# Interface.net
KiCad netlist of a schematic drawn in Altium Designer
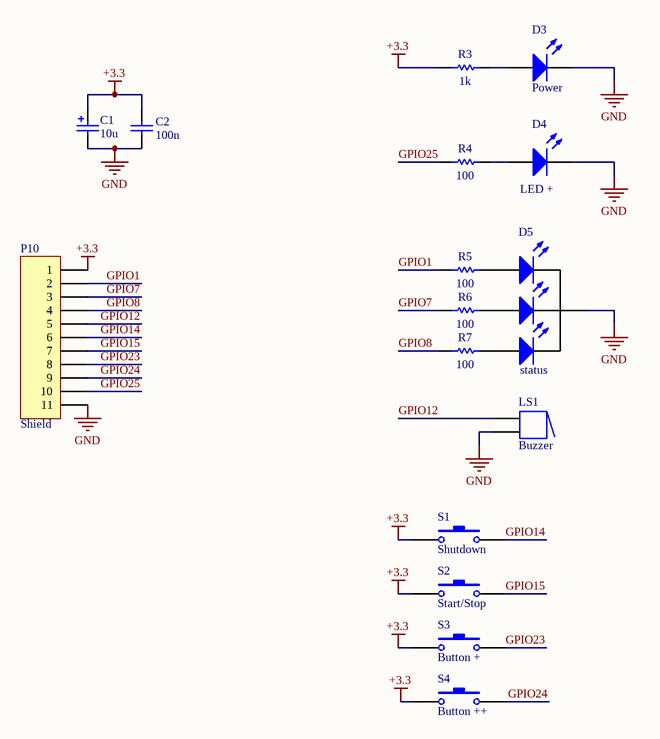
[diagram p0: Interface.SchDoc]

(export (version "E")
  (design (tool "Eeschema 10.0.6"))
  (components
    (comp (ref "C1")
      (value "10u")
      (footprint "Rad5.2")
      (description "Polarized Capacitor (Radial)")
      (fields (field (name "Comment") "Cap Pol1") (field (name "PUBLISHER") "Altium Limited"))
      (libsource (lib "Schlib1") (part "Cap Pol1"))
    )
    (comp (ref "C2")
      (value "100n")
      (footprint "RAD-0.2")
      (description "Capacitor")
      (fields (field (name "Comment") "Cap") (field (name "PUBLISHER") "Altium Limited"))
      (libsource (lib "Schlib1") (part "Cap"))
    )
    (comp (ref "D3")
      (value "Power")
      (footprint "LED_3MM")
      (description "Typical INFRARED GaAs LED")
      (fields (field (name "PUBLISHER") "Altium Limited"))
      (libsource (lib "Schlib1") (part "LED0"))
    )
    (comp (ref "D4")
      (value "LED +")
      (footprint "LED_5mm")
      (description "Typical INFRARED GaAs LED")
      (fields (field (name "PUBLISHER") "Altium Limited"))
      (libsource (lib "Schlib1") (part "LED0"))
    )
    (comp (ref "D5")
      (value "status")
      (footprint "LED RGB")
      (description "Typical INFRARED GaAs LED")
      (fields (field (name "PUBLISHER") "Altium Limited"))
      (libsource (lib "Schlib1") (part "LED_RGB"))
    )
    (comp (ref "LS1")
      (value "Buzzer")
      (footprint "Buzzer")
      (description "Magnetic Transducer Buzzer")
      (fields (field (name "PUBLISHER") "Altium Limited"))
      (libsource (lib "Schlib1") (part "Buzzer"))
    )
    (comp (ref "P10")
      (value "Shield")
      (footprint "Conn_1X11")
      (description "Header, 11-Pin")
      (fields (field (name "PUBLISHER") "Altium Limited"))
      (libsource (lib "Schlib1") (part "Header 11"))
    )
    (comp (ref "R3")
      (value "1k")
      (footprint "AXIAL-0.3")
      (description "Resistor")
      (fields (field (name "Comment") "Res1") (field (name "PUBLISHER") "Altium Limited"))
      (libsource (lib "Miscellaneous Devices") (part "Res1"))
    )
    (comp (ref "R4")
      (value "100")
      (footprint "AXIAL-0.3")
      (description "Resistor")
      (fields (field (name "Comment") "Res1") (field (name "PUBLISHER") "Altium Limited"))
      (libsource (lib "Miscellaneous Devices") (part "Res1"))
    )
    (comp (ref "R5")
      (value "100")
      (footprint "AXIAL-0.3")
      (description "Resistor")
      (fields (field (name "Comment") "Res1") (field (name "PUBLISHER") "Altium Limited"))
      (libsource (lib "Miscellaneous Devices") (part "Res1"))
    )
    (comp (ref "R6")
      (value "100")
      (footprint "AXIAL-0.3")
      (description "Resistor")
      (fields (field (name "Comment") "Res1") (field (name "PUBLISHER") "Altium Limited"))
      (libsource (lib "Miscellaneous Devices") (part "Res1"))
    )
    (comp (ref "R7")
      (value "100")
      (footprint "AXIAL-0.3")
      (description "Resistor")
      (fields (field (name "Comment") "Res1") (field (name "PUBLISHER") "Altium Limited"))
      (libsource (lib "Miscellaneous Devices") (part "Res1"))
    )
    (comp (ref "S1")
      (value "Shutdown")
      (footprint "SW_1825910-6-4")
      (description "Switch")
      (fields (field (name "PUBLISHER") "Altium Limited"))
      (libsource (lib "Schlib1") (part "SW-PB"))
    )
    (comp (ref "S2")
      (value "Start/Stop")
      (footprint "SW_1825910-6-4")
      (description "Switch")
      (fields (field (name "PUBLISHER") "Altium Limited"))
      (libsource (lib "Schlib1") (part "SW-PB"))
    )
    (comp (ref "S3")
      (value "Button +")
      (footprint "SW_1825910-6-4")
      (description "Switch")
      (fields (field (name "PUBLISHER") "Altium Limited"))
      (libsource (lib "Schlib1") (part "SW-PB"))
    )
    (comp (ref "S4")
      (value "Button ++")
      (footprint "SW_1825910-6-4")
      (description "Switch")
      (fields (field (name "PUBLISHER") "Altium Limited"))
      (libsource (lib "Schlib1") (part "SW-PB"))
    )
  )
  (nets
    (net (code "1") (name "+3.3") (class "Default")
      (node (ref "C1") (pin "1") (pinfunction "1_1") (pintype "passive"))
      (node (ref "C2") (pin "1") (pinfunction "1_1") (pintype "passive"))
      (node (ref "P10") (pin "1") (pinfunction "1_1") (pintype "passive"))
      (node (ref "R3") (pin "1") (pinfunction "1_1") (pintype "passive"))
      (node (ref "S1") (pin "1") (pinfunction "1_1") (pintype "passive"))
      (node (ref "S2") (pin "1") (pinfunction "1_1") (pintype "passive"))
      (node (ref "S3") (pin "1") (pinfunction "1_1") (pintype "passive"))
      (node (ref "S4") (pin "1") (pinfunction "1_1") (pintype "passive"))
    )
    (net (code "2") (name "/GPIO1") (class "Default")
      (node (ref "P10") (pin "2") (pinfunction "2_2") (pintype "passive"))
      (node (ref "R5") (pin "1") (pinfunction "1_1") (pintype "passive"))
    )
    (net (code "3") (name "/GPIO7") (class "Default")
      (node (ref "P10") (pin "3") (pinfunction "3_3") (pintype "passive"))
      (node (ref "R6") (pin "1") (pinfunction "1_1") (pintype "passive"))
    )
    (net (code "4") (name "/GPIO8") (class "Default")
      (node (ref "P10") (pin "4") (pinfunction "4_4") (pintype "passive"))
      (node (ref "R7") (pin "1") (pinfunction "1_1") (pintype "passive"))
    )
    (net (code "5") (name "/GPIO12") (class "Default")
      (node (ref "LS1") (pin "1") (pinfunction "1_1") (pintype "passive"))
      (node (ref "P10") (pin "5") (pinfunction "5_5") (pintype "passive"))
    )
    (net (code "6") (name "/GPIO14") (class "Default")
      (node (ref "P10") (pin "6") (pinfunction "6_6") (pintype "passive"))
      (node (ref "S1") (pin "2") (pinfunction "2_2") (pintype "passive"))
    )
    (net (code "7") (name "/GPIO15") (class "Default")
      (node (ref "P10") (pin "7") (pinfunction "7_7") (pintype "passive"))
      (node (ref "S2") (pin "2") (pinfunction "2_2") (pintype "passive"))
    )
    (net (code "8") (name "/GPIO23") (class "Default")
      (node (ref "P10") (pin "8") (pinfunction "8_8") (pintype "passive"))
      (node (ref "S3") (pin "2") (pinfunction "2_2") (pintype "passive"))
    )
    (net (code "9") (name "/GPIO24") (class "Default")
      (node (ref "P10") (pin "9") (pinfunction "9_9") (pintype "passive"))
      (node (ref "S4") (pin "2") (pinfunction "2_2") (pintype "passive"))
    )
    (net (code "10") (name "/GPIO25") (class "Default")
      (node (ref "P10") (pin "10") (pinfunction "10_10") (pintype "passive"))
      (node (ref "R4") (pin "1") (pinfunction "1_1") (pintype "passive"))
    )
    (net (code "11") (name "GND") (class "Default")
      (node (ref "C1") (pin "2") (pinfunction "2_2") (pintype "passive"))
      (node (ref "C2") (pin "2") (pinfunction "2_2") (pintype "passive"))
      (node (ref "D3") (pin "2") (pinfunction "K_2") (pintype "passive"))
      (node (ref "D4") (pin "2") (pinfunction "K_2") (pintype "passive"))
      (node (ref "D5") (pin "2") (pinfunction "K_2") (pintype "passive"))
      (node (ref "LS1") (pin "2") (pinfunction "2_2") (pintype "passive"))
      (node (ref "P10") (pin "11") (pinfunction "11_11") (pintype "passive"))
    )
    (net (code "12") (name "Net-(D3-A)") (class "Default")
      (node (ref "D3") (pin "1") (pinfunction "A_1") (pintype "passive"))
      (node (ref "R3") (pin "2") (pinfunction "2_2") (pintype "passive"))
    )
    (net (code "13") (name "Net-(D4-A)") (class "Default")
      (node (ref "D4") (pin "1") (pinfunction "A_1") (pintype "passive"))
      (node (ref "R4") (pin "2") (pinfunction "2_2") (pintype "passive"))
    )
    (net (code "14") (name "Net-(D5-B)") (class "Default")
      (node (ref "D5") (pin "4") (pinfunction "B_4") (pintype "passive"))
      (node (ref "R7") (pin "2") (pinfunction "2_2") (pintype "passive"))
    )
    (net (code "15") (name "Net-(D5-G)") (class "Default")
      (node (ref "D5") (pin "3") (pinfunction "G_3") (pintype "passive"))
      (node (ref "R6") (pin "2") (pinfunction "2_2") (pintype "passive"))
    )
    (net (code "16") (name "Net-(D5-R)") (class "Default")
      (node (ref "D5") (pin "1") (pinfunction "R_1") (pintype "passive"))
      (node (ref "R5") (pin "2") (pinfunction "2_2") (pintype "passive"))
    )
  )
)
